# MSXII-Controller-Breakout.net
KiCad netlist of a schematic drawn in Altium Designer
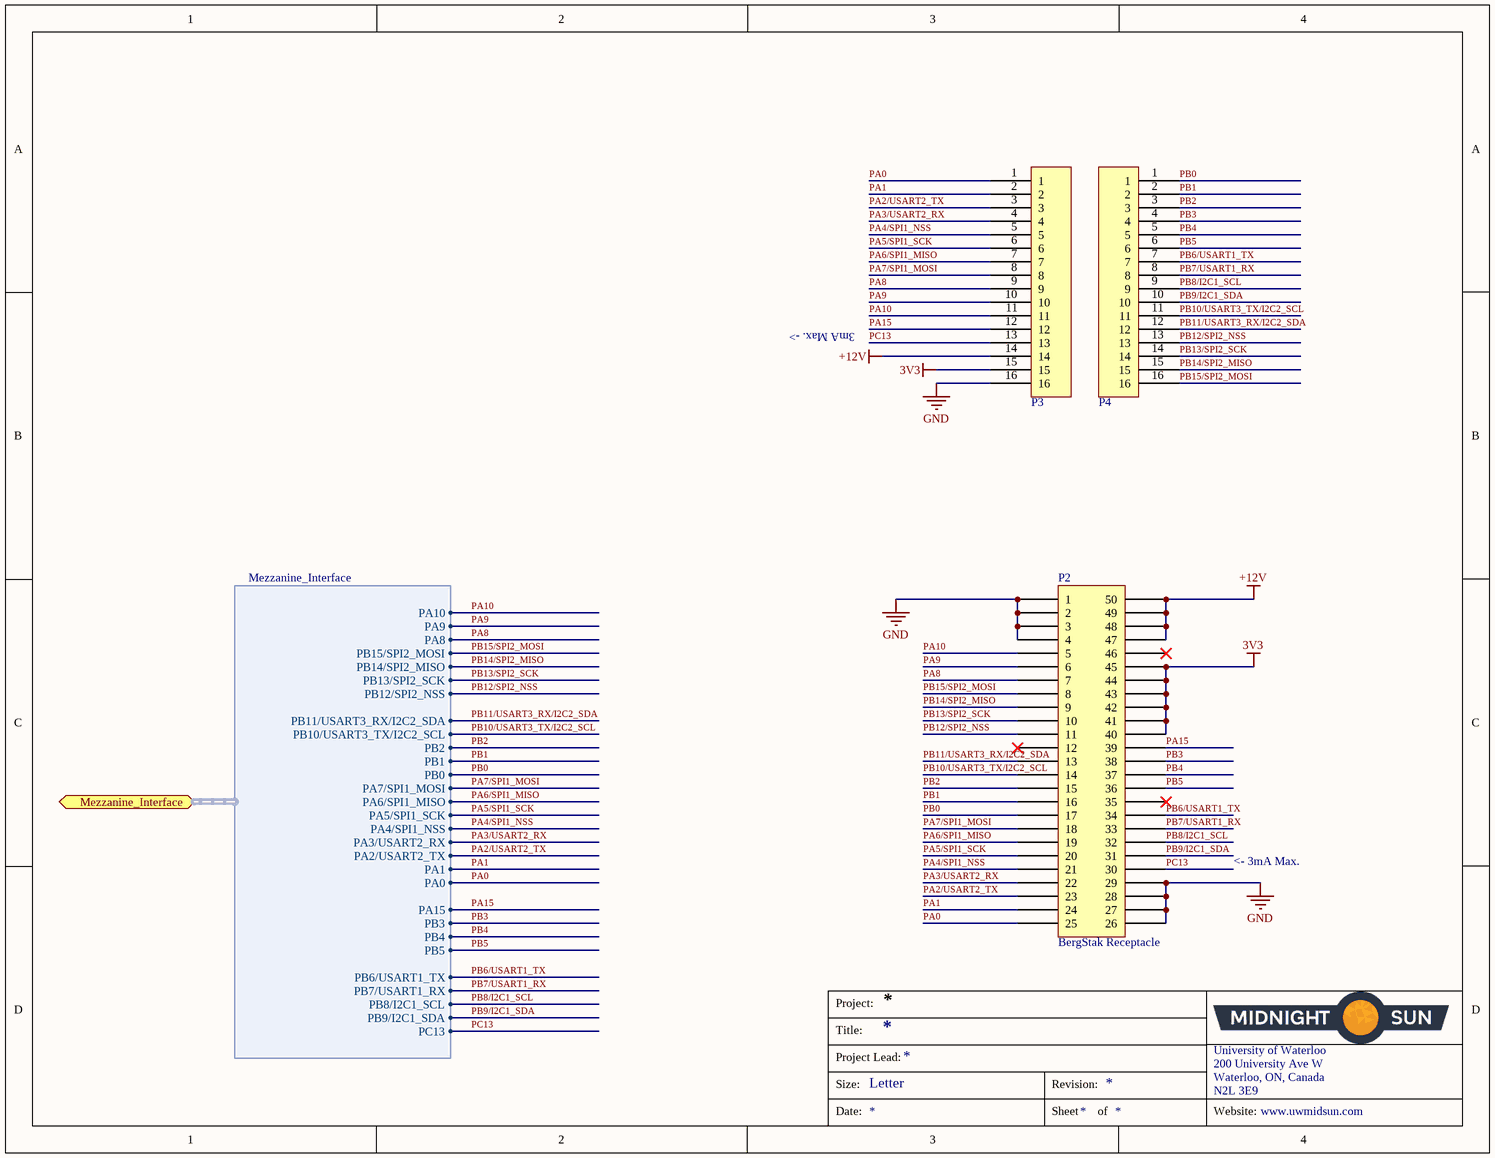
[diagram p0: MSXII-Controller-Breakout.SchDoc]

(export (version "E")
  (design (tool "Eeschema 10.0.6"))
  (components
    (comp (ref "P2")
      (value "BergStak Receptacle")
      (footprint "Bergstak 50 Pos Receptacle")
      (description "50 Position Connector Receptacle, Center Strip Contacts Surface Mount Gold")
      (fields
        (field (name "DIGIKEY PART NUMBER") "609-5227-1-ND")
        (field (name "MANUFACTURER PART NUMBER") "10132798-052100LF")
      )
      (libsource (lib "Midnight Sun Integrated Library") (part "BergStak 50 Position Connector Receptacle"))
    )
    (comp (ref "P3")
      (value "CONN HEADER .100\" SNGL STR 16POS")
      (footprint "Footprints:CONN HEADER .100\" SNGL STR 16POS")
      (description "16 Positions Header, Breakaway Connector 0.100\" (2.54mm) Through Hole Gold")
      (fields (field (name "MFG") "Sullins Connector Solutions"))
      (libsource (lib "Schematic Diagrams") (part "CONN HEADER .100{dblquote} SNGL STR 16POS"))
    )
    (comp (ref "P4")
      (value "CONN HEADER .100\" SNGL STR 16POS")
      (footprint "Footprints:CONN HEADER .100\" SNGL STR 16POS")
      (description "16 Positions Header, Breakaway Connector 0.100\" (2.54mm) Through Hole Gold")
      (fields (field (name "MFG") "Sullins Connector Solutions"))
      (libsource (lib "") (part "CONN HEADER .100{dblquote} SNGL STR 16POS_1"))
    )
  )
  (nets
    (net (code "2") (name "+12V") (class "Default")
      (node (ref "P2") (pin "47") (pinfunction "47_47") (pintype "passive"))
      (node (ref "P2") (pin "48") (pinfunction "48_48") (pintype "passive"))
      (node (ref "P2") (pin "49") (pinfunction "49_49") (pintype "passive"))
      (node (ref "P2") (pin "50") (pinfunction "50_50") (pintype "passive"))
      (node (ref "P3") (pin "14") (pinfunction "14_14") (pintype "passive"))
    )
    (net (code "3") (name "/PA0") (class "Default")
      (node (ref "P2") (pin "25") (pinfunction "25_25") (pintype "passive"))
      (node (ref "P3") (pin "1") (pinfunction "1_1") (pintype "passive"))
    )
    (net (code "4") (name "/PA1") (class "Default")
      (node (ref "P2") (pin "24") (pinfunction "24_24") (pintype "passive"))
      (node (ref "P3") (pin "2") (pinfunction "2_2") (pintype "passive"))
    )
    (net (code "5") (name "/PA2{slash}USART2_TX") (class "Default")
      (node (ref "P2") (pin "23") (pinfunction "23_23") (pintype "passive"))
      (node (ref "P3") (pin "3") (pinfunction "3_3") (pintype "passive"))
    )
    (net (code "6") (name "/PA3{slash}USART2_RX") (class "Default")
      (node (ref "P2") (pin "22") (pinfunction "22_22") (pintype "passive"))
      (node (ref "P3") (pin "4") (pinfunction "4_4") (pintype "passive"))
    )
    (net (code "7") (name "/PA4{slash}SPI1_NSS") (class "Default")
      (node (ref "P2") (pin "21") (pinfunction "21_21") (pintype "passive"))
      (node (ref "P3") (pin "5") (pinfunction "5_5") (pintype "passive"))
    )
    (net (code "8") (name "/PA5{slash}SPI1_SCK") (class "Default")
      (node (ref "P2") (pin "20") (pinfunction "20_20") (pintype "passive"))
      (node (ref "P3") (pin "6") (pinfunction "6_6") (pintype "passive"))
    )
    (net (code "9") (name "/PA6{slash}SPI1_MISO") (class "Default")
      (node (ref "P2") (pin "19") (pinfunction "19_19") (pintype "passive"))
      (node (ref "P3") (pin "7") (pinfunction "7_7") (pintype "passive"))
    )
    (net (code "10") (name "/PA7{slash}SPI1_MOSI") (class "Default")
      (node (ref "P2") (pin "18") (pinfunction "18_18") (pintype "passive"))
      (node (ref "P3") (pin "8") (pinfunction "8_8") (pintype "passive"))
    )
    (net (code "11") (name "/PA8") (class "Default")
      (node (ref "P2") (pin "7") (pinfunction "7_7") (pintype "passive"))
      (node (ref "P3") (pin "9") (pinfunction "9_9") (pintype "passive"))
    )
    (net (code "12") (name "/PA9") (class "Default")
      (node (ref "P2") (pin "6") (pinfunction "6_6") (pintype "passive"))
      (node (ref "P3") (pin "10") (pinfunction "10_10") (pintype "passive"))
    )
    (net (code "13") (name "/PA10") (class "Default")
      (node (ref "P2") (pin "5") (pinfunction "5_5") (pintype "passive"))
      (node (ref "P3") (pin "11") (pinfunction "11_11") (pintype "passive"))
    )
    (net (code "14") (name "/PA15") (class "Default")
      (node (ref "P2") (pin "39") (pinfunction "39_39") (pintype "passive"))
      (node (ref "P3") (pin "12") (pinfunction "12_12") (pintype "passive"))
    )
    (net (code "15") (name "/PB0") (class "Default")
      (node (ref "P2") (pin "17") (pinfunction "17_17") (pintype "passive"))
      (node (ref "P4") (pin "1") (pinfunction "1_1") (pintype "passive"))
    )
    (net (code "16") (name "/PB1") (class "Default")
      (node (ref "P2") (pin "16") (pinfunction "16_16") (pintype "passive"))
      (node (ref "P4") (pin "2") (pinfunction "2_2") (pintype "passive"))
    )
    (net (code "17") (name "/PB2") (class "Default")
      (node (ref "P2") (pin "15") (pinfunction "15_15") (pintype "passive"))
      (node (ref "P4") (pin "3") (pinfunction "3_3") (pintype "passive"))
    )
    (net (code "18") (name "/PB3") (class "Default")
      (node (ref "P2") (pin "38") (pinfunction "38_38") (pintype "passive"))
      (node (ref "P4") (pin "4") (pinfunction "4_4") (pintype "passive"))
    )
    (net (code "19") (name "/PB4") (class "Default")
      (node (ref "P2") (pin "37") (pinfunction "37_37") (pintype "passive"))
      (node (ref "P4") (pin "5") (pinfunction "5_5") (pintype "passive"))
    )
    (net (code "20") (name "/PB5") (class "Default")
      (node (ref "P2") (pin "36") (pinfunction "36_36") (pintype "passive"))
      (node (ref "P4") (pin "6") (pinfunction "6_6") (pintype "passive"))
    )
    (net (code "21") (name "/PB6{slash}USART1_TX") (class "Default")
      (node (ref "P2") (pin "34") (pinfunction "34_34") (pintype "passive"))
      (node (ref "P4") (pin "7") (pinfunction "7_7") (pintype "passive"))
    )
    (net (code "22") (name "/PB7{slash}USART1_RX") (class "Default")
      (node (ref "P2") (pin "33") (pinfunction "33_33") (pintype "passive"))
      (node (ref "P4") (pin "8") (pinfunction "8_8") (pintype "passive"))
    )
    (net (code "23") (name "/PB8{slash}I2C1_SCL") (class "Default")
      (node (ref "P2") (pin "32") (pinfunction "32_32") (pintype "passive"))
      (node (ref "P4") (pin "9") (pinfunction "9_9") (pintype "passive"))
    )
    (net (code "24") (name "/PB9{slash}I2C1_SDA") (class "Default")
      (node (ref "P2") (pin "31") (pinfunction "31_31") (pintype "passive"))
      (node (ref "P4") (pin "10") (pinfunction "10_10") (pintype "passive"))
    )
    (net (code "25") (name "/PB10{slash}USART3_TX{slash}I2C2_SCL") (class "Default")
      (node (ref "P2") (pin "14") (pinfunction "14_14") (pintype "passive"))
      (node (ref "P4") (pin "11") (pinfunction "11_11") (pintype "passive"))
    )
    (net (code "26") (name "/PB11{slash}USART3_RX{slash}I2C2_SDA") (class "Default")
      (node (ref "P2") (pin "13") (pinfunction "13_13") (pintype "passive"))
      (node (ref "P4") (pin "12") (pinfunction "12_12") (pintype "passive"))
    )
    (net (code "27") (name "/PB12{slash}SPI2_NSS") (class "Default")
      (node (ref "P2") (pin "11") (pinfunction "11_11") (pintype "passive"))
      (node (ref "P4") (pin "13") (pinfunction "13_13") (pintype "passive"))
    )
    (net (code "28") (name "/PB13{slash}SPI2_SCK") (class "Default")
      (node (ref "P2") (pin "10") (pinfunction "10_10") (pintype "passive"))
      (node (ref "P4") (pin "14") (pinfunction "14_14") (pintype "passive"))
    )
    (net (code "29") (name "/PB14{slash}SPI2_MISO") (class "Default")
      (node (ref "P2") (pin "9") (pinfunction "9_9") (pintype "passive"))
      (node (ref "P4") (pin "15") (pinfunction "15_15") (pintype "passive"))
    )
    (net (code "30") (name "/PB15{slash}SPI2_MOSI") (class "Default")
      (node (ref "P2") (pin "8") (pinfunction "8_8") (pintype "passive"))
      (node (ref "P4") (pin "16") (pinfunction "16_16") (pintype "passive"))
    )
    (net (code "31") (name "/PC13") (class "Default")
      (node (ref "P2") (pin "30") (pinfunction "30_30") (pintype "passive"))
      (node (ref "P3") (pin "13") (pinfunction "13_13") (pintype "passive"))
    )
    (net (code "33") (name "3V3") (class "Default")
      (node (ref "P2") (pin "40") (pinfunction "40_40") (pintype "passive"))
      (node (ref "P2") (pin "41") (pinfunction "41_41") (pintype "passive"))
      (node (ref "P2") (pin "42") (pinfunction "42_42") (pintype "passive"))
      (node (ref "P2") (pin "43") (pinfunction "43_43") (pintype "passive"))
      (node (ref "P2") (pin "44") (pinfunction "44_44") (pintype "passive"))
      (node (ref "P2") (pin "45") (pinfunction "45_45") (pintype "passive"))
      (node (ref "P3") (pin "15") (pinfunction "15_15") (pintype "passive"))
    )
    (net (code "34") (name "GND") (class "Default")
      (node (ref "P2") (pin "1") (pinfunction "1_1") (pintype "passive"))
      (node (ref "P2") (pin "2") (pinfunction "2_2") (pintype "passive"))
      (node (ref "P2") (pin "26") (pinfunction "26_26") (pintype "passive"))
      (node (ref "P2") (pin "27") (pinfunction "27_27") (pintype "passive"))
      (node (ref "P2") (pin "28") (pinfunction "28_28") (pintype "passive"))
      (node (ref "P2") (pin "29") (pinfunction "29_29") (pintype "passive"))
      (node (ref "P2") (pin "3") (pinfunction "3_3") (pintype "passive"))
      (node (ref "P2") (pin "4") (pinfunction "4_4") (pintype "passive"))
      (node (ref "P3") (pin "16") (pinfunction "16_16") (pintype "passive"))
    )
    (net (code "35") (name "unconnected-(P2-Pad12)") (class "Default")
      (node (ref "P2") (pin "12") (pinfunction "12_12") (pintype "passive+no_connect"))
    )
    (net (code "36") (name "unconnected-(P2-Pad35)") (class "Default")
      (node (ref "P2") (pin "35") (pinfunction "35_35") (pintype "passive+no_connect"))
    )
    (net (code "37") (name "unconnected-(P2-Pad46)") (class "Default")
      (node (ref "P2") (pin "46") (pinfunction "46_46") (pintype "passive+no_connect"))
    )
  )
)
